# Sheet1.net
KiCad netlist of a schematic drawn in Altium Designer
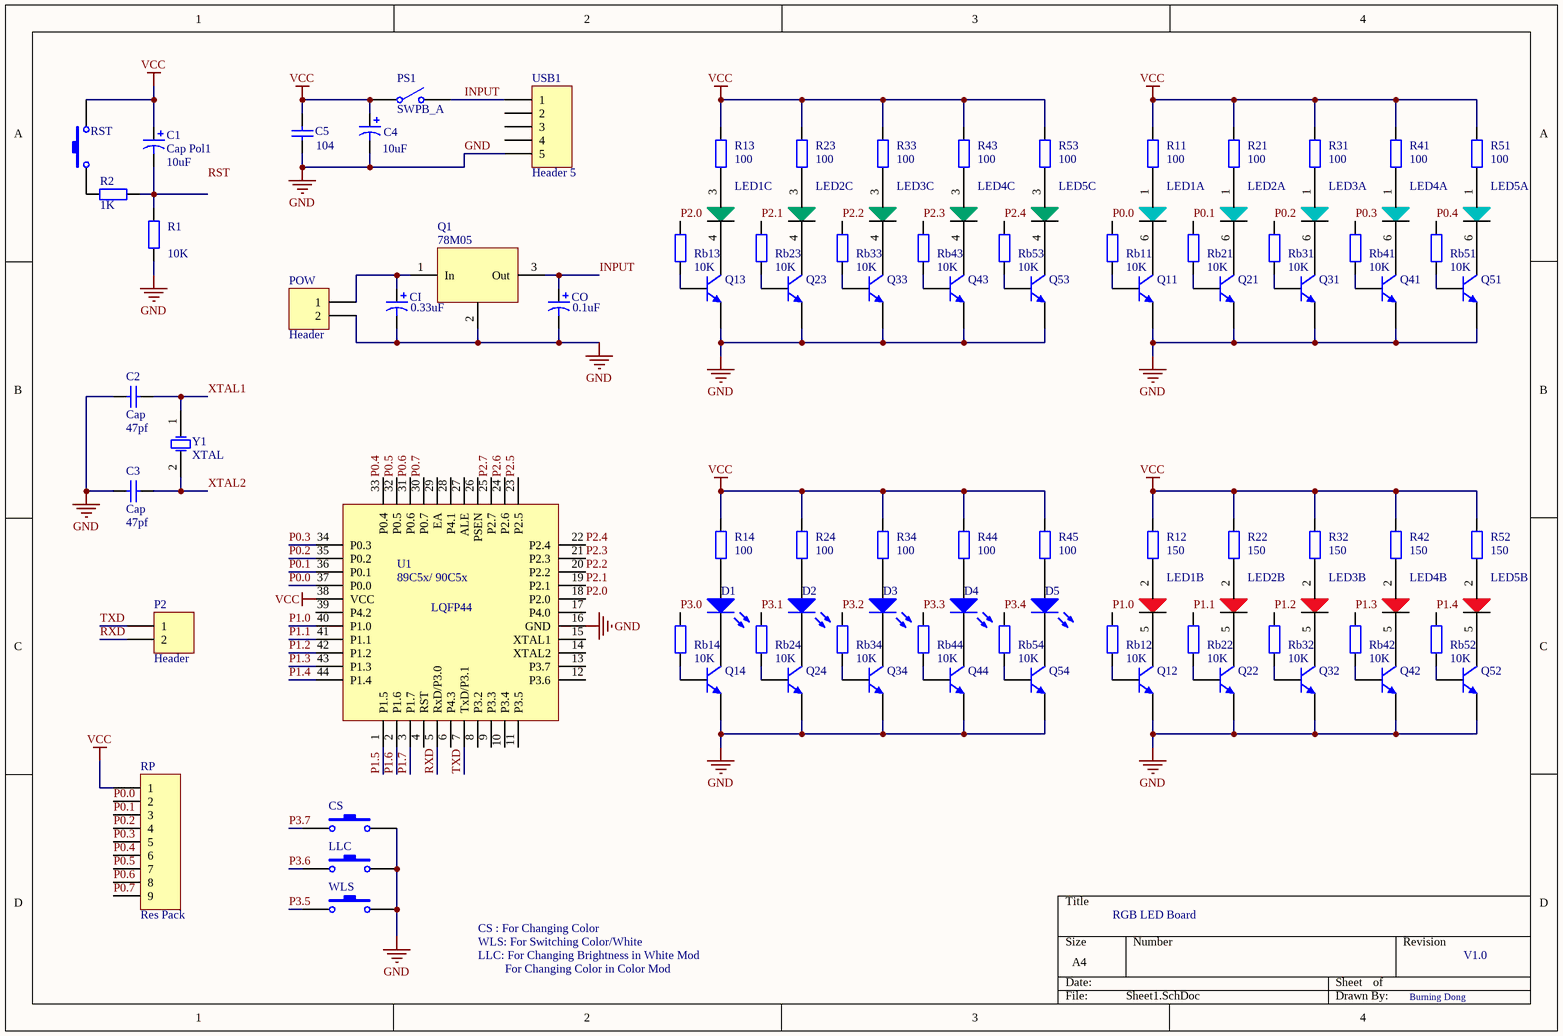
[diagram p0: Sheet1.SchDoc]

(export (version "E")
  (design (tool "Eeschema 10.0.6"))
  (components
    (comp (ref "C1")
      (value "Cap Pol1")
      (footprint "C0805")
      (description "Polarized Capacitor (Radial)")
      (fields (field (name "ALTIUM_VALUE") "10uF") (field (name "PUBLISHER") "Altium Limited"))
      (libsource (lib "Miscellaneous Devices") (part "Cap Pol1"))
    )
    (comp (ref "C2")
      (value "Cap")
      (footprint "C0805")
      (description "Capacitor")
      (fields (field (name "ALTIUM_VALUE") "47pf") (field (name "PUBLISHER") "Altium Limited"))
      (libsource (lib "Miscellaneous Devices") (part "Cap"))
    )
    (comp (ref "C3")
      (value "Cap")
      (footprint "C0805")
      (description "Capacitor")
      (fields (field (name "ALTIUM_VALUE") "47pf") (field (name "PUBLISHER") "Altium Limited"))
      (libsource (lib "Miscellaneous Devices") (part "Cap"))
    )
    (comp (ref "C4")
      (value "10uF")
      (footprint "C0805")
      (description "Polarized Capacitor (Radial)")
      (fields (field (name "Comment") "Cap Pol1") (field (name "PUBLISHER") "Altium Limited"))
      (libsource (lib "Miscellaneous Devices") (part "Cap Pol1"))
    )
    (comp (ref "C5")
      (value "104")
      (footprint "C1206")
      (description "Capacitor")
      (fields (field (name "Comment") "Cap") (field (name "PUBLISHER") "Altium Limited"))
      (libsource (lib "Miscellaneous Devices") (part "Cap"))
    )
    (comp (ref "CI")
      (value "0.33uF")
      (footprint "C0805")
      (description "Polarized Capacitor (Radial)")
      (fields (field (name "Comment") "Cap Pol1") (field (name "PUBLISHER") "Altium Limited"))
      (libsource (lib "Miscellaneous Devices") (part "Cap Pol1"))
    )
    (comp (ref "CO")
      (value "0.1uF")
      (footprint "C0805")
      (description "Polarized Capacitor (Radial)")
      (fields (field (name "Comment") "Cap Pol1") (field (name "PUBLISHER") "Altium Limited"))
      (libsource (lib "Miscellaneous Devices") (part "Cap Pol1"))
    )
    (comp (ref "CS")
      (value "SW-PB")
      (footprint "SW_A")
      (description "Switch")
      (fields (field (name "PUBLISHER") "Altium Limited"))
      (libsource (lib "Miscellaneous Devices") (part "SW-PB"))
    )
    (comp (ref "D1")
      (value "LED0")
      (footprint "LED 5050 NoneRGB")
      (description "Typical INFRARED GaAs LED")
      (fields (field (name "PUBLISHER") "Altium Limited"))
      (libsource (lib "Miscellaneous Devices") (part "LED0"))
    )
    (comp (ref "D2")
      (value "LED0")
      (footprint "LED 5050 NoneRGB")
      (description "Typical INFRARED GaAs LED")
      (fields (field (name "PUBLISHER") "Altium Limited"))
      (libsource (lib "Miscellaneous Devices") (part "LED0"))
    )
    (comp (ref "D3")
      (value "LED0")
      (footprint "LED 5050 NoneRGB")
      (description "Typical INFRARED GaAs LED")
      (fields (field (name "PUBLISHER") "Altium Limited"))
      (libsource (lib "Miscellaneous Devices") (part "LED0"))
    )
    (comp (ref "D4")
      (value "LED0")
      (footprint "LED 5050 NoneRGB")
      (description "Typical INFRARED GaAs LED")
      (fields (field (name "PUBLISHER") "Altium Limited"))
      (libsource (lib "Miscellaneous Devices") (part "LED0"))
    )
    (comp (ref "D5")
      (value "LED0")
      (footprint "LED 5050 NoneRGB")
      (description "Typical INFRARED GaAs LED")
      (fields (field (name "PUBLISHER") "Altium Limited"))
      (libsource (lib "Miscellaneous Devices") (part "LED0"))
    )
    (comp (ref "LED1") (value "RGB LED") (footprint "LED 5050") (libsource (lib "Usual") (part "RGB LED")))
    (comp (ref "LED2") (value "RGB LED") (footprint "LED 5050") (libsource (lib "Usual") (part "RGB LED")))
    (comp (ref "LED3") (value "RGB LED") (footprint "LED 5050") (libsource (lib "Usual") (part "RGB LED")))
    (comp (ref "LED4") (value "RGB LED") (footprint "LED 5050") (libsource (lib "Usual") (part "RGB LED")))
    (comp (ref "LED5") (value "RGB LED") (footprint "LED 5050") (libsource (lib "Usual") (part "RGB LED")))
    (comp (ref "LLC")
      (value "SW-PB")
      (footprint "SW_A")
      (description "Switch")
      (fields (field (name "PUBLISHER") "Altium Limited"))
      (libsource (lib "Miscellaneous Devices") (part "SW-PB"))
    )
    (comp (ref "P2")
      (value "Header")
      (footprint "HDR1X2")
      (description "Header, 2-Pin")
      (fields (field (name "PUBLISHER") "Altium Limited"))
      (libsource (lib "Miscellaneous Connectors") (part "Header 2"))
    )
    (comp (ref "POW")
      (value "Header")
      (footprint "HDR1X2")
      (description "Header, 2-Pin")
      (fields (field (name "PUBLISHER") "Altium Limited"))
      (libsource (lib "") (part "Header 2_1"))
    )
    (comp (ref "PS1")
      (value "SWPB_A")
      (footprint "SW_B")
      (description "Single-Pole, Single-Throw Switch")
      (fields (field (name "PUBLISHER") "Altium Limited"))
      (libsource (lib "Miscellaneous Devices") (part "SW-SPST"))
    )
    (comp (ref "Q1") (value "78M05") (footprint "TO_252") (libsource (lib "Usual") (part "78XX")))
    (comp (ref "Q11")
      (value "s8050")
      (footprint "SOT-23_N")
      (description "NPN General Purpose Amplifier")
      (fields (field (name "PUBLISHER") "Altium Limited"))
      (libsource (lib "Miscellaneous Devices") (part "2N3904"))
    )
    (comp (ref "Q12")
      (value "s8050")
      (footprint "SOT-23_N")
      (description "NPN General Purpose Amplifier")
      (fields (field (name "PUBLISHER") "Altium Limited"))
      (libsource (lib "Miscellaneous Devices") (part "2N3904"))
    )
    (comp (ref "Q13")
      (value "s8050")
      (footprint "SOT-23_N")
      (description "NPN General Purpose Amplifier")
      (fields (field (name "PUBLISHER") "Altium Limited"))
      (libsource (lib "Miscellaneous Devices") (part "2N3904"))
    )
    (comp (ref "Q14")
      (value "s8050")
      (footprint "SOT-23_N")
      (description "NPN General Purpose Amplifier")
      (fields (field (name "PUBLISHER") "Altium Limited"))
      (libsource (lib "Miscellaneous Devices") (part "2N3904"))
    )
    (comp (ref "Q21")
      (value "s8050")
      (footprint "SOT-23_N")
      (description "NPN General Purpose Amplifier")
      (fields (field (name "PUBLISHER") "Altium Limited"))
      (libsource (lib "Miscellaneous Devices") (part "2N3904"))
    )
    (comp (ref "Q22")
      (value "s8050")
      (footprint "SOT-23_N")
      (description "NPN General Purpose Amplifier")
      (fields (field (name "PUBLISHER") "Altium Limited"))
      (libsource (lib "Miscellaneous Devices") (part "2N3904"))
    )
    (comp (ref "Q23")
      (value "s8050")
      (footprint "SOT-23_N")
      (description "NPN General Purpose Amplifier")
      (fields (field (name "PUBLISHER") "Altium Limited"))
      (libsource (lib "Miscellaneous Devices") (part "2N3904"))
    )
    (comp (ref "Q24")
      (value "s8050")
      (footprint "SOT-23_N")
      (description "NPN General Purpose Amplifier")
      (fields (field (name "PUBLISHER") "Altium Limited"))
      (libsource (lib "Miscellaneous Devices") (part "2N3904"))
    )
    (comp (ref "Q31")
      (value "s8050")
      (footprint "SOT-23_N")
      (description "NPN General Purpose Amplifier")
      (fields (field (name "PUBLISHER") "Altium Limited"))
      (libsource (lib "Miscellaneous Devices") (part "2N3904"))
    )
    (comp (ref "Q32")
      (value "s8050")
      (footprint "SOT-23_N")
      (description "NPN General Purpose Amplifier")
      (fields (field (name "PUBLISHER") "Altium Limited"))
      (libsource (lib "Miscellaneous Devices") (part "2N3904"))
    )
    (comp (ref "Q33")
      (value "s8050")
      (footprint "SOT-23_N")
      (description "NPN General Purpose Amplifier")
      (fields (field (name "PUBLISHER") "Altium Limited"))
      (libsource (lib "Miscellaneous Devices") (part "2N3904"))
    )
    (comp (ref "Q34")
      (value "s8050")
      (footprint "SOT-23_N")
      (description "NPN General Purpose Amplifier")
      (fields (field (name "PUBLISHER") "Altium Limited"))
      (libsource (lib "Miscellaneous Devices") (part "2N3904"))
    )
    (comp (ref "Q41")
      (value "s8050")
      (footprint "SOT-23_N")
      (description "NPN General Purpose Amplifier")
      (fields (field (name "PUBLISHER") "Altium Limited"))
      (libsource (lib "Miscellaneous Devices") (part "2N3904"))
    )
    (comp (ref "Q42")
      (value "s8050")
      (footprint "SOT-23_N")
      (description "NPN General Purpose Amplifier")
      (fields (field (name "PUBLISHER") "Altium Limited"))
      (libsource (lib "Miscellaneous Devices") (part "2N3904"))
    )
    (comp (ref "Q43")
      (value "s8050")
      (footprint "SOT-23_N")
      (description "NPN General Purpose Amplifier")
      (fields (field (name "PUBLISHER") "Altium Limited"))
      (libsource (lib "Miscellaneous Devices") (part "2N3904"))
    )
    (comp (ref "Q44")
      (value "s8050")
      (footprint "SOT-23_N")
      (description "NPN General Purpose Amplifier")
      (fields (field (name "PUBLISHER") "Altium Limited"))
      (libsource (lib "Miscellaneous Devices") (part "2N3904"))
    )
    (comp (ref "Q51")
      (value "s8050")
      (footprint "SOT-23_N")
      (description "NPN General Purpose Amplifier")
      (fields (field (name "PUBLISHER") "Altium Limited"))
      (libsource (lib "Miscellaneous Devices") (part "2N3904"))
    )
    (comp (ref "Q52")
      (value "s8050")
      (footprint "SOT-23_N")
      (description "NPN General Purpose Amplifier")
      (fields (field (name "PUBLISHER") "Altium Limited"))
      (libsource (lib "Miscellaneous Devices") (part "2N3904"))
    )
    (comp (ref "Q53")
      (value "s8050")
      (footprint "SOT-23_N")
      (description "NPN General Purpose Amplifier")
      (fields (field (name "PUBLISHER") "Altium Limited"))
      (libsource (lib "Miscellaneous Devices") (part "2N3904"))
    )
    (comp (ref "Q54")
      (value "s8050")
      (footprint "SOT-23_N")
      (description "NPN General Purpose Amplifier")
      (fields (field (name "PUBLISHER") "Altium Limited"))
      (libsource (lib "Miscellaneous Devices") (part "2N3904"))
    )
    (comp (ref "R1")
      (value "10K")
      (footprint "6-0805_N")
      (description "Resistor")
      (fields (field (name "Comment") "Res2") (field (name "PUBLISHER") "Altium Limited"))
      (libsource (lib "Miscellaneous Devices") (part "Res2"))
    )
    (comp (ref "R2")
      (value "1K")
      (footprint "6-0805_N")
      (description "Resistor")
      (fields (field (name "Comment") "Res2") (field (name "PUBLISHER") "Altium Limited"))
      (libsource (lib "") (part "Res2_1"))
    )
    (comp (ref "R11")
      (value "100")
      (footprint "6-0805_N")
      (description "Resistor")
      (fields (field (name "Comment") "Res2") (field (name "PUBLISHER") "Altium Limited"))
      (libsource (lib "Miscellaneous Devices") (part "Res2"))
    )
    (comp (ref "R12")
      (value "150")
      (footprint "6-0805_N")
      (description "Resistor")
      (fields (field (name "Comment") "Res2") (field (name "PUBLISHER") "Altium Limited"))
      (libsource (lib "Miscellaneous Devices") (part "Res2"))
    )
    (comp (ref "R13")
      (value "100")
      (footprint "6-0805_N")
      (description "Resistor")
      (fields (field (name "Comment") "Res2") (field (name "PUBLISHER") "Altium Limited"))
      (libsource (lib "Miscellaneous Devices") (part "Res2"))
    )
    (comp (ref "R14")
      (value "100")
      (footprint "6-0805_N")
      (description "Resistor")
      (fields (field (name "Comment") "Res2") (field (name "PUBLISHER") "Altium Limited"))
      (libsource (lib "Miscellaneous Devices") (part "Res2"))
    )
    (comp (ref "R21")
      (value "100")
      (footprint "6-0805_N")
      (description "Resistor")
      (fields (field (name "Comment") "Res2") (field (name "PUBLISHER") "Altium Limited"))
      (libsource (lib "Miscellaneous Devices") (part "Res2"))
    )
    (comp (ref "R22")
      (value "150")
      (footprint "6-0805_N")
      (description "Resistor")
      (fields (field (name "Comment") "Res2") (field (name "PUBLISHER") "Altium Limited"))
      (libsource (lib "Miscellaneous Devices") (part "Res2"))
    )
    (comp (ref "R23")
      (value "100")
      (footprint "6-0805_N")
      (description "Resistor")
      (fields (field (name "Comment") "Res2") (field (name "PUBLISHER") "Altium Limited"))
      (libsource (lib "Miscellaneous Devices") (part "Res2"))
    )
    (comp (ref "R24")
      (value "100")
      (footprint "6-0805_N")
      (description "Resistor")
      (fields (field (name "Comment") "Res2") (field (name "PUBLISHER") "Altium Limited"))
      (libsource (lib "Miscellaneous Devices") (part "Res2"))
    )
    (comp (ref "R31")
      (value "100")
      (footprint "6-0805_N")
      (description "Resistor")
      (fields (field (name "Comment") "Res2") (field (name "PUBLISHER") "Altium Limited"))
      (libsource (lib "Miscellaneous Devices") (part "Res2"))
    )
    (comp (ref "R32")
      (value "150")
      (footprint "6-0805_N")
      (description "Resistor")
      (fields (field (name "Comment") "Res2") (field (name "PUBLISHER") "Altium Limited"))
      (libsource (lib "Miscellaneous Devices") (part "Res2"))
    )
    (comp (ref "R33")
      (value "100")
      (footprint "6-0805_N")
      (description "Resistor")
      (fields (field (name "Comment") "Res2") (field (name "PUBLISHER") "Altium Limited"))
      (libsource (lib "Miscellaneous Devices") (part "Res2"))
    )
    (comp (ref "R34")
      (value "100")
      (footprint "6-0805_N")
      (description "Resistor")
      (fields (field (name "Comment") "Res2") (field (name "PUBLISHER") "Altium Limited"))
      (libsource (lib "Miscellaneous Devices") (part "Res2"))
    )
    (comp (ref "R41")
      (value "100")
      (footprint "6-0805_N")
      (description "Resistor")
      (fields (field (name "Comment") "Res2") (field (name "PUBLISHER") "Altium Limited"))
      (libsource (lib "Miscellaneous Devices") (part "Res2"))
    )
    (comp (ref "R42")
      (value "150")
      (footprint "6-0805_N")
      (description "Resistor")
      (fields (field (name "Comment") "Res2") (field (name "PUBLISHER") "Altium Limited"))
      (libsource (lib "Miscellaneous Devices") (part "Res2"))
    )
    (comp (ref "R43")
      (value "100")
      (footprint "6-0805_N")
      (description "Resistor")
      (fields (field (name "Comment") "Res2") (field (name "PUBLISHER") "Altium Limited"))
      (libsource (lib "Miscellaneous Devices") (part "Res2"))
    )
    (comp (ref "R44")
      (value "100")
      (footprint "6-0805_N")
      (description "Resistor")
      (fields (field (name "Comment") "Res2") (field (name "PUBLISHER") "Altium Limited"))
      (libsource (lib "Miscellaneous Devices") (part "Res2"))
    )
    (comp (ref "R45")
      (value "100")
      (footprint "6-0805_N")
      (description "Resistor")
      (fields (field (name "Comment") "Res2") (field (name "PUBLISHER") "Altium Limited"))
      (libsource (lib "Miscellaneous Devices") (part "Res2"))
    )
    (comp (ref "R51")
      (value "100")
      (footprint "6-0805_N")
      (description "Resistor")
      (fields (field (name "Comment") "Res2") (field (name "PUBLISHER") "Altium Limited"))
      (libsource (lib "Miscellaneous Devices") (part "Res2"))
    )
    (comp (ref "R52")
      (value "150")
      (footprint "6-0805_N")
      (description "Resistor")
      (fields (field (name "Comment") "Res2") (field (name "PUBLISHER") "Altium Limited"))
      (libsource (lib "Miscellaneous Devices") (part "Res2"))
    )
    (comp (ref "R53")
      (value "100")
      (footprint "6-0805_N")
      (description "Resistor")
      (fields (field (name "Comment") "Res2") (field (name "PUBLISHER") "Altium Limited"))
      (libsource (lib "Miscellaneous Devices") (part "Res2"))
    )
    (comp (ref "Rb11")
      (value "10K")
      (footprint "6-0805_N")
      (description "Resistor")
      (fields (field (name "Comment") "Res2") (field (name "PUBLISHER") "Altium Limited"))
      (libsource (lib "Miscellaneous Devices") (part "Res2"))
    )
    (comp (ref "Rb12")
      (value "10K")
      (footprint "6-0805_N")
      (description "Resistor")
      (fields (field (name "Comment") "Res2") (field (name "PUBLISHER") "Altium Limited"))
      (libsource (lib "Miscellaneous Devices") (part "Res2"))
    )
    (comp (ref "Rb13")
      (value "10K")
      (footprint "6-0805_N")
      (description "Resistor")
      (fields (field (name "Comment") "Res2") (field (name "PUBLISHER") "Altium Limited"))
      (libsource (lib "Miscellaneous Devices") (part "Res2"))
    )
    (comp (ref "Rb14")
      (value "10K")
      (footprint "6-0805_N")
      (description "Resistor")
      (fields (field (name "Comment") "Res2") (field (name "PUBLISHER") "Altium Limited"))
      (libsource (lib "Miscellaneous Devices") (part "Res2"))
    )
    (comp (ref "Rb21")
      (value "10K")
      (footprint "6-0805_N")
      (description "Resistor")
      (fields (field (name "Comment") "Res2") (field (name "PUBLISHER") "Altium Limited"))
      (libsource (lib "Miscellaneous Devices") (part "Res2"))
    )
    (comp (ref "Rb22")
      (value "10K")
      (footprint "6-0805_N")
      (description "Resistor")
      (fields (field (name "Comment") "Res2") (field (name "PUBLISHER") "Altium Limited"))
      (libsource (lib "Miscellaneous Devices") (part "Res2"))
    )
    (comp (ref "Rb23")
      (value "10K")
      (footprint "6-0805_N")
      (description "Resistor")
      (fields (field (name "Comment") "Res2") (field (name "PUBLISHER") "Altium Limited"))
      (libsource (lib "Miscellaneous Devices") (part "Res2"))
    )
    (comp (ref "Rb24")
      (value "10K")
      (footprint "6-0805_N")
      (description "Resistor")
      (fields (field (name "Comment") "Res2") (field (name "PUBLISHER") "Altium Limited"))
      (libsource (lib "Miscellaneous Devices") (part "Res2"))
    )
    (comp (ref "Rb31")
      (value "10K")
      (footprint "6-0805_N")
      (description "Resistor")
      (fields (field (name "Comment") "Res2") (field (name "PUBLISHER") "Altium Limited"))
      (libsource (lib "Miscellaneous Devices") (part "Res2"))
    )
    (comp (ref "Rb32")
      (value "10K")
      (footprint "6-0805_N")
      (description "Resistor")
      (fields (field (name "Comment") "Res2") (field (name "PUBLISHER") "Altium Limited"))
      (libsource (lib "Miscellaneous Devices") (part "Res2"))
    )
    (comp (ref "Rb33")
      (value "10K")
      (footprint "6-0805_N")
      (description "Resistor")
      (fields (field (name "Comment") "Res2") (field (name "PUBLISHER") "Altium Limited"))
      (libsource (lib "Miscellaneous Devices") (part "Res2"))
    )
    (comp (ref "Rb34")
      (value "10K")
      (footprint "6-0805_N")
      (description "Resistor")
      (fields (field (name "Comment") "Res2") (field (name "PUBLISHER") "Altium Limited"))
      (libsource (lib "Miscellaneous Devices") (part "Res2"))
    )
    (comp (ref "Rb41")
      (value "10K")
      (footprint "6-0805_N")
      (description "Resistor")
      (fields (field (name "Comment") "Res2") (field (name "PUBLISHER") "Altium Limited"))
      (libsource (lib "Miscellaneous Devices") (part "Res2"))
    )
    (comp (ref "Rb42")
      (value "10K")
      (footprint "6-0805_N")
      (description "Resistor")
      (fields (field (name "Comment") "Res2") (field (name "PUBLISHER") "Altium Limited"))
      (libsource (lib "Miscellaneous Devices") (part "Res2"))
    )
    (comp (ref "Rb43")
      (value "10K")
      (footprint "6-0805_N")
      (description "Resistor")
      (fields (field (name "Comment") "Res2") (field (name "PUBLISHER") "Altium Limited"))
      (libsource (lib "Miscellaneous Devices") (part "Res2"))
    )
    (comp (ref "Rb44")
      (value "10K")
      (footprint "6-0805_N")
      (description "Resistor")
      (fields (field (name "Comment") "Res2") (field (name "PUBLISHER") "Altium Limited"))
      (libsource (lib "Miscellaneous Devices") (part "Res2"))
    )
    (comp (ref "Rb51")
      (value "10K")
      (footprint "6-0805_N")
      (description "Resistor")
      (fields (field (name "Comment") "Res2") (field (name "PUBLISHER") "Altium Limited"))
      (libsource (lib "Miscellaneous Devices") (part "Res2"))
    )
    (comp (ref "Rb52")
      (value "10K")
      (footprint "6-0805_N")
      (description "Resistor")
      (fields (field (name "Comment") "Res2") (field (name "PUBLISHER") "Altium Limited"))
      (libsource (lib "Miscellaneous Devices") (part "Res2"))
    )
    (comp (ref "Rb53")
      (value "10K")
      (footprint "6-0805_N")
      (description "Resistor")
      (fields (field (name "Comment") "Res2") (field (name "PUBLISHER") "Altium Limited"))
      (libsource (lib "Miscellaneous Devices") (part "Res2"))
    )
    (comp (ref "Rb54")
      (value "10K")
      (footprint "6-0805_N")
      (description "Resistor")
      (fields (field (name "Comment") "Res2") (field (name "PUBLISHER") "Altium Limited"))
      (libsource (lib "Miscellaneous Devices") (part "Res2"))
    )
    (comp (ref "RP")
      (value "Res Pack")
      (footprint "HDR1X9")
      (description "Header, 9-Pin")
      (fields (field (name "PUBLISHER") "Altium Limited"))
      (libsource (lib "Miscellaneous Connectors") (part "Header 9"))
    )
    (comp (ref "RST")
      (value "SW-PB")
      (footprint "SW_A")
      (description "Switch")
      (fields (field (name "PUBLISHER") "Altium Limited"))
      (libsource (lib "Miscellaneous Devices") (part "SW-PB"))
    )
    (comp (ref "U1")
      (value "89C5x/ 90C5x")
      (footprint "TQFP44_N")
      (libsource (lib "STC") (part "89C5x/ 90C5x"))
    )
    (comp (ref "USB1")
      (value "Header 5")
      (footprint "Micro_USB_B")
      (description "Header, 5-Pin")
      (fields (field (name "PUBLISHER") "Altium Limited"))
      (libsource (lib "Miscellaneous Connectors") (part "Header 5"))
    )
    (comp (ref "WLS")
      (value "SW-PB")
      (footprint "SW_A")
      (description "Switch")
      (fields (field (name "PUBLISHER") "Altium Limited"))
      (libsource (lib "Miscellaneous Devices") (part "SW-PB"))
    )
    (comp (ref "Y1")
      (value "XTAL")
      (footprint "XTAL")
      (description "Crystal Oscillator")
      (fields (field (name "PUBLISHER") "Altium Limited"))
      (libsource (lib "Miscellaneous Devices") (part "XTAL"))
    )
  )
  (nets
    (net (code "1") (name "/INPUT") (class "Default")
      (node (ref "CO") (pin "1") (pinfunction "1_1") (pintype "passive"))
      (node (ref "PS1") (pin "2") (pinfunction "NO_2") (pintype "passive"))
      (node (ref "Q1") (pin "3") (pinfunction "Out_3") (pintype "passive"))
      (node (ref "USB1") (pin "1") (pinfunction "1_1") (pintype "passive"))
    )
    (net (code "2") (name "/P0.0") (class "Default")
      (node (ref "RP") (pin "2") (pinfunction "2_2") (pintype "passive"))
      (node (ref "Rb11") (pin "1") (pinfunction "1_1") (pintype "passive"))
      (node (ref "U1") (pin "37") (pinfunction "P0.0_37") (pintype "passive"))
    )
    (net (code "3") (name "/P0.1") (class "Default")
      (node (ref "RP") (pin "3") (pinfunction "3_3") (pintype "passive"))
      (node (ref "Rb21") (pin "1") (pinfunction "1_1") (pintype "passive"))
      (node (ref "U1") (pin "36") (pinfunction "P0.1_36") (pintype "passive"))
    )
    (net (code "4") (name "/P0.2") (class "Default")
      (node (ref "RP") (pin "4") (pinfunction "4_4") (pintype "passive"))
      (node (ref "Rb31") (pin "1") (pinfunction "1_1") (pintype "passive"))
      (node (ref "U1") (pin "35") (pinfunction "P0.2_35") (pintype "passive"))
    )
    (net (code "5") (name "/P0.3") (class "Default")
      (node (ref "RP") (pin "5") (pinfunction "5_5") (pintype "passive"))
      (node (ref "Rb41") (pin "1") (pinfunction "1_1") (pintype "passive"))
      (node (ref "U1") (pin "34") (pinfunction "P0.3_34") (pintype "passive"))
    )
    (net (code "6") (name "/P0.4") (class "Default")
      (node (ref "RP") (pin "6") (pinfunction "6_6") (pintype "passive"))
      (node (ref "Rb51") (pin "1") (pinfunction "1_1") (pintype "passive"))
      (node (ref "U1") (pin "33") (pinfunction "P0.4_33") (pintype "passive"))
    )
    (net (code "7") (name "/P0.5") (class "Default")
      (node (ref "RP") (pin "7") (pinfunction "7_7") (pintype "passive"))
      (node (ref "U1") (pin "32") (pinfunction "P0.5_32") (pintype "passive"))
    )
    (net (code "8") (name "/P0.6") (class "Default")
      (node (ref "RP") (pin "8") (pinfunction "8_8") (pintype "passive"))
      (node (ref "U1") (pin "31") (pinfunction "P0.6_31") (pintype "passive"))
    )
    (net (code "9") (name "/P0.7") (class "Default")
      (node (ref "RP") (pin "9") (pinfunction "9_9") (pintype "passive"))
      (node (ref "U1") (pin "30") (pinfunction "P0.7_30") (pintype "passive"))
    )
    (net (code "10") (name "/P1.0") (class "Default")
      (node (ref "Rb12") (pin "1") (pinfunction "1_1") (pintype "passive"))
      (node (ref "U1") (pin "40") (pinfunction "P1.0_40") (pintype "passive"))
    )
    (net (code "11") (name "/P1.1") (class "Default")
      (node (ref "Rb22") (pin "1") (pinfunction "1_1") (pintype "passive"))
      (node (ref "U1") (pin "41") (pinfunction "P1.1_41") (pintype "passive"))
    )
    (net (code "12") (name "/P1.2") (class "Default")
      (node (ref "Rb32") (pin "1") (pinfunction "1_1") (pintype "passive"))
      (node (ref "U1") (pin "42") (pinfunction "P1.2_42") (pintype "passive"))
    )
    (net (code "13") (name "/P1.3") (class "Default")
      (node (ref "Rb42") (pin "1") (pinfunction "1_1") (pintype "passive"))
      (node (ref "U1") (pin "43") (pinfunction "P1.3_43") (pintype "passive"))
    )
    (net (code "14") (name "/P1.4") (class "Default")
      (node (ref "Rb52") (pin "1") (pinfunction "1_1") (pintype "passive"))
      (node (ref "U1") (pin "44") (pinfunction "P1.4_44") (pintype "passive"))
    )
    (net (code "15") (name "/P1.5") (class "Default")
      (node (ref "U1") (pin "1") (pinfunction "P1.5_1") (pintype "passive"))
    )
    (net (code "16") (name "/P1.6") (class "Default")
      (node (ref "U1") (pin "2") (pinfunction "P1.6_2") (pintype "passive"))
    )
    (net (code "17") (name "/P1.7") (class "Default")
      (node (ref "U1") (pin "3") (pinfunction "P1.7_3") (pintype "passive"))
    )
    (net (code "18") (name "/P2.0") (class "Default")
      (node (ref "Rb13") (pin "1") (pinfunction "1_1") (pintype "passive"))
      (node (ref "U1") (pin "18") (pinfunction "P2.0_18") (pintype "passive"))
    )
    (net (code "19") (name "/P2.1") (class "Default")
      (node (ref "Rb23") (pin "1") (pinfunction "1_1") (pintype "passive"))
      (node (ref "U1") (pin "19") (pinfunction "P2.1_19") (pintype "passive"))
    )
    (net (code "20") (name "/P2.2") (class "Default")
      (node (ref "Rb33") (pin "1") (pinfunction "1_1") (pintype "passive"))
      (node (ref "U1") (pin "20") (pinfunction "P2.2_20") (pintype "passive"))
    )
    (net (code "21") (name "/P2.3") (class "Default")
      (node (ref "Rb43") (pin "1") (pinfunction "1_1") (pintype "passive"))
      (node (ref "U1") (pin "21") (pinfunction "P2.3_21") (pintype "passive"))
    )
    (net (code "22") (name "/P2.4") (class "Default")
      (node (ref "Rb53") (pin "1") (pinfunction "1_1") (pintype "passive"))
      (node (ref "U1") (pin "22") (pinfunction "P2.4_22") (pintype "passive"))
    )
    (net (code "23") (name "/P2.5") (class "Default")
      (node (ref "U1") (pin "23") (pinfunction "P2.5_23") (pintype "passive"))
    )
    (net (code "24") (name "/P2.6") (class "Default")
      (node (ref "U1") (pin "24") (pinfunction "P2.6_24") (pintype "passive"))
    )
    (net (code "25") (name "/P2.7") (class "Default")
      (node (ref "U1") (pin "25") (pinfunction "P2.7_25") (pintype "passive"))
    )
    (net (code "26") (name "/P3.0") (class "Default")
      (node (ref "Rb14") (pin "1") (pinfunction "1_1") (pintype "passive"))
    )
    (net (code "27") (name "/P3.1") (class "Default")
      (node (ref "Rb24") (pin "1") (pinfunction "1_1") (pintype "passive"))
    )
    (net (code "28") (name "/P3.2") (class "Default")
      (node (ref "Rb34") (pin "1") (pinfunction "1_1") (pintype "passive"))
    )
    (net (code "29") (name "/P3.3") (class "Default")
      (node (ref "Rb44") (pin "1") (pinfunction "1_1") (pintype "passive"))
    )
    (net (code "30") (name "/P3.4") (class "Default")
      (node (ref "Rb54") (pin "1") (pinfunction "1_1") (pintype "passive"))
    )
    (net (code "31") (name "/P3.5") (class "Default")
      (node (ref "WLS") (pin "1") (pinfunction "1_1") (pintype "passive"))
    )
    (net (code "32") (name "/P3.6") (class "Default")
      (node (ref "LLC") (pin "1") (pinfunction "1_1") (pintype "passive"))
    )
    (net (code "33") (name "/P3.7") (class "Default")
      (node (ref "CS") (pin "1") (pinfunction "1_1") (pintype "passive"))
    )
    (net (code "35") (name "/RXD") (class "Default")
      (node (ref "P2") (pin "2") (pinfunction "2_2") (pintype "passive"))
      (node (ref "U1") (pin "5") (pinfunction "RxD/P3.0_5") (pintype "passive"))
    )
    (net (code "36") (name "/TXD") (class "Default")
      (node (ref "P2") (pin "1") (pinfunction "1_1") (pintype "passive"))
      (node (ref "U1") (pin "7") (pinfunction "TxD/P3.1_7") (pintype "passive"))
    )
    (net (code "37") (name "/XTAL1") (class "Default")
      (node (ref "C2") (pin "2") (pinfunction "2_2") (pintype "passive"))
      (node (ref "Y1") (pin "1") (pinfunction "OSC1_1") (pintype "passive"))
    )
    (net (code "38") (name "/XTAL2") (class "Default")
      (node (ref "C3") (pin "2") (pinfunction "2_2") (pintype "passive"))
      (node (ref "Y1") (pin "2") (pinfunction "OSC2_2") (pintype "passive"))
    )
    (net (code "39") (name "GND") (class "Default")
      (node (ref "C2") (pin "1") (pinfunction "1_1") (pintype "passive"))
      (node (ref "C3") (pin "1") (pinfunction "1_1") (pintype "passive"))
      (node (ref "C4") (pin "2") (pinfunction "2_2") (pintype "passive"))
      (node (ref "C5") (pin "2") (pinfunction "2_2") (pintype "passive"))
      (node (ref "CI") (pin "2") (pinfunction "2_2") (pintype "passive"))
      (node (ref "CO") (pin "2") (pinfunction "2_2") (pintype "passive"))
      (node (ref "CS") (pin "2") (pinfunction "2_2") (pintype "passive"))
      (node (ref "LLC") (pin "2") (pinfunction "2_2") (pintype "passive"))
      (node (ref "POW") (pin "2") (pinfunction "2_2") (pintype "passive"))
      (node (ref "Q1") (pin "2") (pinfunction "Com_2") (pintype "passive"))
      (node (ref "Q11") (pin "1") (pinfunction "E_1") (pintype "passive"))
      (node (ref "Q12") (pin "1") (pinfunction "E_1") (pintype "passive"))
      (node (ref "Q13") (pin "1") (pinfunction "E_1") (pintype "passive"))
      (node (ref "Q14") (pin "1") (pinfunction "E_1") (pintype "passive"))
      (node (ref "Q21") (pin "1") (pinfunction "E_1") (pintype "passive"))
      (node (ref "Q22") (pin "1") (pinfunction "E_1") (pintype "passive"))
      (node (ref "Q23") (pin "1") (pinfunction "E_1") (pintype "passive"))
      (node (ref "Q24") (pin "1") (pinfunction "E_1") (pintype "passive"))
      (node (ref "Q31") (pin "1") (pinfunction "E_1") (pintype "passive"))
      (node (ref "Q32") (pin "1") (pinfunction "E_1") (pintype "passive"))
      (node (ref "Q33") (pin "1") (pinfunction "E_1") (pintype "passive"))
      (node (ref "Q34") (pin "1") (pinfunction "E_1") (pintype "passive"))
      (node (ref "Q41") (pin "1") (pinfunction "E_1") (pintype "passive"))
      (node (ref "Q42") (pin "1") (pinfunction "E_1") (pintype "passive"))
      (node (ref "Q43") (pin "1") (pinfunction "E_1") (pintype "passive"))
      (node (ref "Q44") (pin "1") (pinfunction "E_1") (pintype "passive"))
      (node (ref "Q51") (pin "1") (pinfunction "E_1") (pintype "passive"))
      (node (ref "Q52") (pin "1") (pinfunction "E_1") (pintype "passive"))
      (node (ref "Q53") (pin "1") (pinfunction "E_1") (pintype "passive"))
      (node (ref "Q54") (pin "1") (pinfunction "E_1") (pintype "passive"))
      (node (ref "R1") (pin "2") (pinfunction "2_2") (pintype "passive"))
      (node (ref "U1") (pin "16") (pinfunction "GND_16") (pintype "passive"))
      (node (ref "USB1") (pin "5") (pinfunction "5_5") (pintype "passive"))
      (node (ref "WLS") (pin "2") (pinfunction "2_2") (pintype "passive"))
    )
    (net (code "40") (name "Net-(C1-Pad2)") (class "Default")
      (node (ref "C1") (pin "2") (pinfunction "2_2") (pintype "passive"))
      (node (ref "R1") (pin "1") (pinfunction "1_1") (pintype "passive"))
      (node (ref "R2") (pin "1") (pinfunction "1_1") (pintype "passive"))
    )
    (net (code "41") (name "Net-(D1-A)") (class "Default")
      (node (ref "D1") (pin "1") (pinfunction "A_1") (pintype "passive"))
      (node (ref "R14") (pin "2") (pinfunction "2_2") (pintype "passive"))
    )
    (net (code "42") (name "Net-(D1-K)") (class "Default")
      (node (ref "D1") (pin "2") (pinfunction "K_2") (pintype "passive"))
      (node (ref "Q14") (pin "3") (pinfunction "C_3") (pintype "passive"))
    )
    (net (code "43") (name "Net-(D2-A)") (class "Default")
      (node (ref "D2") (pin "1") (pinfunction "A_1") (pintype "passive"))
      (node (ref "R24") (pin "2") (pinfunction "2_2") (pintype "passive"))
    )
    (net (code "44") (name "Net-(D2-K)") (class "Default")
      (node (ref "D2") (pin "2") (pinfunction "K_2") (pintype "passive"))
      (node (ref "Q24") (pin "3") (pinfunction "C_3") (pintype "passive"))
    )
    (net (code "45") (name "Net-(D3-A)") (class "Default")
      (node (ref "D3") (pin "1") (pinfunction "A_1") (pintype "passive"))
      (node (ref "R34") (pin "2") (pinfunction "2_2") (pintype "passive"))
    )
    (net (code "46") (name "Net-(D3-K)") (class "Default")
      (node (ref "D3") (pin "2") (pinfunction "K_2") (pintype "passive"))
      (node (ref "Q34") (pin "3") (pinfunction "C_3") (pintype "passive"))
    )
    (net (code "47") (name "Net-(D4-A)") (class "Default")
      (node (ref "D4") (pin "1") (pinfunction "A_1") (pintype "passive"))
      (node (ref "R44") (pin "2") (pinfunction "2_2") (pintype "passive"))
    )
    (net (code "48") (name "Net-(D4-K)") (class "Default")
      (node (ref "D4") (pin "2") (pinfunction "K_2") (pintype "passive"))
      (node (ref "Q44") (pin "3") (pinfunction "C_3") (pintype "passive"))
    )
    (net (code "49") (name "Net-(D5-A)") (class "Default")
      (node (ref "D5") (pin "1") (pinfunction "A_1") (pintype "passive"))
      (node (ref "R45") (pin "2") (pinfunction "2_2") (pintype "passive"))
    )
    (net (code "50") (name "Net-(D5-K)") (class "Default")
      (node (ref "D5") (pin "2") (pinfunction "K_2") (pintype "passive"))
      (node (ref "Q54") (pin "3") (pinfunction "C_3") (pintype "passive"))
    )
    (net (code "51") (name "Net-(LED1A-B+)") (class "Default")
      (node (ref "LED1") (pin "1") (pinfunction "B+_1") (pintype "passive"))
      (node (ref "R11") (pin "2") (pinfunction "2_2") (pintype "passive"))
    )
    (net (code "52") (name "Net-(LED1A-B-)") (class "Default")
      (node (ref "LED1") (pin "6") (pinfunction "B-_6") (pintype "passive"))
      (node (ref "Q11") (pin "3") (pinfunction "C_3") (pintype "passive"))
    )
    (net (code "53") (name "Net-(LED1B-B+)") (class "Default")
      (node (ref "LED1") (pin "2") (pinfunction "B+_2") (pintype "passive"))
      (node (ref "R12") (pin "2") (pinfunction "2_2") (pintype "passive"))
    )
    (net (code "54") (name "Net-(LED1B-B-)") (class "Default")
      (node (ref "LED1") (pin "5") (pinfunction "B-_5") (pintype "passive"))
      (node (ref "Q12") (pin "3") (pinfunction "C_3") (pintype "passive"))
    )
    (net (code "55") (name "Net-(LED1C-B+)") (class "Default")
      (node (ref "LED1") (pin "3") (pinfunction "B+_3") (pintype "passive"))
      (node (ref "R13") (pin "2") (pinfunction "2_2") (pintype "passive"))
    )
    (net (code "56") (name "Net-(LED1C-B-)") (class "Default")
      (node (ref "LED1") (pin "4") (pinfunction "B-_4") (pintype "passive"))
      (node (ref "Q13") (pin "3") (pinfunction "C_3") (pintype "passive"))
    )
    (net (code "57") (name "Net-(LED2A-B+)") (class "Default")
      (node (ref "LED2") (pin "1") (pinfunction "B+_1") (pintype "passive"))
      (node (ref "R21") (pin "2") (pinfunction "2_2") (pintype "passive"))
    )
    (net (code "58") (name "Net-(LED2A-B-)") (class "Default")
      (node (ref "LED2") (pin "6") (pinfunction "B-_6") (pintype "passive"))
      (node (ref "Q21") (pin "3") (pinfunction "C_3") (pintype "passive"))
    )
    (net (code "59") (name "Net-(LED2B-B+)") (class "Default")
      (node (ref "LED2") (pin "2") (pinfunction "B+_2") (pintype "passive"))
      (node (ref "R22") (pin "2") (pinfunction "2_2") (pintype "passive"))
    )
    (net (code "60") (name "Net-(LED2B-B-)") (class "Default")
      (node (ref "LED2") (pin "5") (pinfunction "B-_5") (pintype "passive"))
      (node (ref "Q22") (pin "3") (pinfunction "C_3") (pintype "passive"))
    )
    (net (code "61") (name "Net-(LED2C-B+)") (class "Default")
      (node (ref "LED2") (pin "3") (pinfunction "B+_3") (pintype "passive"))
      (node (ref "R23") (pin "2") (pinfunction "2_2") (pintype "passive"))
    )
    (net (code "62") (name "Net-(LED2C-B-)") (class "Default")
      (node (ref "LED2") (pin "4") (pinfunction "B-_4") (pintype "passive"))
      (node (ref "Q23") (pin "3") (pinfunction "C_3") (pintype "passive"))
    )
    (net (code "63") (name "Net-(LED3A-B+)") (class "Default")
      (node (ref "LED3") (pin "1") (pinfunction "B+_1") (pintype "passive"))
      (node (ref "R31") (pin "2") (pinfunction "2_2") (pintype "passive"))
    )
    (net (code "64") (name "Net-(LED3A-B-)") (class "Default")
      (node (ref "LED3") (pin "6") (pinfunction "B-_6") (pintype "passive"))
      (node (ref "Q31") (pin "3") (pinfunction "C_3") (pintype "passive"))
    )
    (net (code "65") (name "Net-(LED3B-B+)") (class "Default")
      (node (ref "LED3") (pin "2") (pinfunction "B+_2") (pintype "passive"))
      (node (ref "R32") (pin "2") (pinfunction "2_2") (pintype "passive"))
    )
    (net (code "66") (name "Net-(LED3B-B-)") (class "Default")
      (node (ref "LED3") (pin "5") (pinfunction "B-_5") (pintype "passive"))
      (node (ref "Q32") (pin "3") (pinfunction "C_3") (pintype "passive"))
    )
    (net (code "67") (name "Net-(LED3C-B+)") (class "Default")
      (node (ref "LED3") (pin "3") (pinfunction "B+_3") (pintype "passive"))
      (node (ref "R33") (pin "2") (pinfunction "2_2") (pintype "passive"))
    )
    (net (code "68") (name "Net-(LED3C-B-)") (class "Default")
      (node (ref "LED3") (pin "4") (pinfunction "B-_4") (pintype "passive"))
      (node (ref "Q33") (pin "3") (pinfunction "C_3") (pintype "passive"))
    )
    (net (code "69") (name "Net-(LED4A-B+)") (class "Default")
      (node (ref "LED4") (pin "1") (pinfunction "B+_1") (pintype "passive"))
      (node (ref "R41") (pin "2") (pinfunction "2_2") (pintype "passive"))
    )
    (net (code "70") (name "Net-(LED4A-B-)") (class "Default")
      (node (ref "LED4") (pin "6") (pinfunction "B-_6") (pintype "passive"))
      (node (ref "Q41") (pin "3") (pinfunction "C_3") (pintype "passive"))
    )
    (net (code "71") (name "Net-(LED4B-B+)") (class "Default")
      (node (ref "LED4") (pin "2") (pinfunction "B+_2") (pintype "passive"))
      (node (ref "R42") (pin "2") (pinfunction "2_2") (pintype "passive"))
    )
    (net (code "72") (name "Net-(LED4B-B-)") (class "Default")
      (node (ref "LED4") (pin "5") (pinfunction "B-_5") (pintype "passive"))
      (node (ref "Q42") (pin "3") (pinfunction "C_3") (pintype "passive"))
    )
    (net (code "73") (name "Net-(LED4C-B+)") (class "Default")
      (node (ref "LED4") (pin "3") (pinfunction "B+_3") (pintype "passive"))
      (node (ref "R43") (pin "2") (pinfunction "2_2") (pintype "passive"))
    )
    (net (code "74") (name "Net-(LED4C-B-)") (class "Default")
      (node (ref "LED4") (pin "4") (pinfunction "B-_4") (pintype "passive"))
      (node (ref "Q43") (pin "3") (pinfunction "C_3") (pintype "passive"))
    )
    (net (code "75") (name "Net-(LED5A-B+)") (class "Default")
      (node (ref "LED5") (pin "1") (pinfunction "B+_1") (pintype "passive"))
      (node (ref "R51") (pin "2") (pinfunction "2_2") (pintype "passive"))
    )
    (net (code "76") (name "Net-(LED5A-B-)") (class "Default")
      (node (ref "LED5") (pin "6") (pinfunction "B-_6") (pintype "passive"))
      (node (ref "Q51") (pin "3") (pinfunction "C_3") (pintype "passive"))
    )
    (net (code "77") (name "Net-(LED5B-B+)") (class "Default")
      (node (ref "LED5") (pin "2") (pinfunction "B+_2") (pintype "passive"))
      (node (ref "R52") (pin "2") (pinfunction "2_2") (pintype "passive"))
    )
    (net (code "78") (name "Net-(LED5B-B-)") (class "Default")
      (node (ref "LED5") (pin "5") (pinfunction "B-_5") (pintype "passive"))
      (node (ref "Q52") (pin "3") (pinfunction "C_3") (pintype "passive"))
    )
    (net (code "79") (name "Net-(LED5C-B+)") (class "Default")
      (node (ref "LED5") (pin "3") (pinfunction "B+_3") (pintype "passive"))
      (node (ref "R53") (pin "2") (pinfunction "2_2") (pintype "passive"))
    )
    (net (code "80") (name "Net-(LED5C-B-)") (class "Default")
      (node (ref "LED5") (pin "4") (pinfunction "B-_4") (pintype "passive"))
      (node (ref "Q53") (pin "3") (pinfunction "C_3") (pintype "passive"))
    )
    (net (code "81") (name "Net-(Q1-In)") (class "Default")
      (node (ref "CI") (pin "1") (pinfunction "1_1") (pintype "passive"))
      (node (ref "POW") (pin "1") (pinfunction "1_1") (pintype "passive"))
      (node (ref "Q1") (pin "1") (pinfunction "In_1") (pintype "passive"))
    )
    (net (code "82") (name "Net-(Q11-B)") (class "Default")
      (node (ref "Q11") (pin "2") (pinfunction "B_2") (pintype "passive"))
      (node (ref "Rb11") (pin "2") (pinfunction "2_2") (pintype "passive"))
    )
    (net (code "83") (name "Net-(Q12-B)") (class "Default")
      (node (ref "Q12") (pin "2") (pinfunction "B_2") (pintype "passive"))
      (node (ref "Rb12") (pin "2") (pinfunction "2_2") (pintype "passive"))
    )
    (net (code "84") (name "Net-(Q13-B)") (class "Default")
      (node (ref "Q13") (pin "2") (pinfunction "B_2") (pintype "passive"))
      (node (ref "Rb13") (pin "2") (pinfunction "2_2") (pintype "passive"))
    )
    (net (code "85") (name "Net-(Q14-B)") (class "Default")
      (node (ref "Q14") (pin "2") (pinfunction "B_2") (pintype "passive"))
      (node (ref "Rb14") (pin "2") (pinfunction "2_2") (pintype "passive"))
    )
    (net (code "86") (name "Net-(Q21-B)") (class "Default")
      (node (ref "Q21") (pin "2") (pinfunction "B_2") (pintype "passive"))
      (node (ref "Rb21") (pin "2") (pinfunction "2_2") (pintype "passive"))
    )
    (net (code "87") (name "Net-(Q22-B)") (class "Default")
      (node (ref "Q22") (pin "2") (pinfunction "B_2") (pintype "passive"))
      (node (ref "Rb22") (pin "2") (pinfunction "2_2") (pintype "passive"))
    )
    (net (code "88") (name "Net-(Q23-B)") (class "Default")
      (node (ref "Q23") (pin "2") (pinfunction "B_2") (pintype "passive"))
      (node (ref "Rb23") (pin "2") (pinfunction "2_2") (pintype "passive"))
    )
    (net (code "89") (name "Net-(Q24-B)") (class "Default")
      (node (ref "Q24") (pin "2") (pinfunction "B_2") (pintype "passive"))
      (node (ref "Rb24") (pin "2") (pinfunction "2_2") (pintype "passive"))
    )
    (net (code "90") (name "Net-(Q31-B)") (class "Default")
      (node (ref "Q31") (pin "2") (pinfunction "B_2") (pintype "passive"))
      (node (ref "Rb31") (pin "2") (pinfunction "2_2") (pintype "passive"))
    )
    (net (code "91") (name "Net-(Q32-B)") (class "Default")
      (node (ref "Q32") (pin "2") (pinfunction "B_2") (pintype "passive"))
      (node (ref "Rb32") (pin "2") (pinfunction "2_2") (pintype "passive"))
    )
    (net (code "92") (name "Net-(Q33-B)") (class "Default")
      (node (ref "Q33") (pin "2") (pinfunction "B_2") (pintype "passive"))
      (node (ref "Rb33") (pin "2") (pinfunction "2_2") (pintype "passive"))
    )
    (net (code "93") (name "Net-(Q34-B)") (class "Default")
      (node (ref "Q34") (pin "2") (pinfunction "B_2") (pintype "passive"))
      (node (ref "Rb34") (pin "2") (pinfunction "2_2") (pintype "passive"))
    )
    (net (code "94") (name "Net-(Q41-B)") (class "Default")
      (node (ref "Q41") (pin "2") (pinfunction "B_2") (pintype "passive"))
      (node (ref "Rb41") (pin "2") (pinfunction "2_2") (pintype "passive"))
    )
    (net (code "95") (name "Net-(Q42-B)") (class "Default")
      (node (ref "Q42") (pin "2") (pinfunction "B_2") (pintype "passive"))
      (node (ref "Rb42") (pin "2") (pinfunction "2_2") (pintype "passive"))
    )
    (net (code "96") (name "Net-(Q43-B)") (class "Default")
      (node (ref "Q43") (pin "2") (pinfunction "B_2") (pintype "passive"))
      (node (ref "Rb43") (pin "2") (pinfunction "2_2") (pintype "passive"))
    )
    (net (code "97") (name "Net-(Q44-B)") (class "Default")
      (node (ref "Q44") (pin "2") (pinfunction "B_2") (pintype "passive"))
      (node (ref "Rb44") (pin "2") (pinfunction "2_2") (pintype "passive"))
    )
    (net (code "98") (name "Net-(Q51-B)") (class "Default")
      (node (ref "Q51") (pin "2") (pinfunction "B_2") (pintype "passive"))
      (node (ref "Rb51") (pin "2") (pinfunction "2_2") (pintype "passive"))
    )
    (net (code "99") (name "Net-(Q52-B)") (class "Default")
      (node (ref "Q52") (pin "2") (pinfunction "B_2") (pintype "passive"))
      (node (ref "Rb52") (pin "2") (pinfunction "2_2") (pintype "passive"))
    )
    (net (code "100") (name "Net-(Q53-B)") (class "Default")
      (node (ref "Q53") (pin "2") (pinfunction "B_2") (pintype "passive"))
      (node (ref "Rb53") (pin "2") (pinfunction "2_2") (pintype "passive"))
    )
    (net (code "101") (name "Net-(Q54-B)") (class "Default")
      (node (ref "Q54") (pin "2") (pinfunction "B_2") (pintype "passive"))
      (node (ref "Rb54") (pin "2") (pinfunction "2_2") (pintype "passive"))
    )
    (net (code "102") (name "Net-(R2-Pad2)") (class "Default")
      (node (ref "R2") (pin "2") (pinfunction "2_2") (pintype "passive"))
      (node (ref "RST") (pin "1") (pinfunction "1_1") (pintype "passive"))
    )
    (net (code "103") (name "VCC") (class "Default")
      (node (ref "C1") (pin "1") (pinfunction "1_1") (pintype "passive"))
      (node (ref "C4") (pin "1") (pinfunction "1_1") (pintype "passive"))
      (node (ref "C5") (pin "1") (pinfunction "1_1") (pintype "passive"))
      (node (ref "PS1") (pin "1") (pinfunction "COMMON_1") (pintype "passive"))
      (node (ref "R11") (pin "1") (pinfunction "1_1") (pintype "passive"))
      (node (ref "R12") (pin "1") (pinfunction "1_1") (pintype "passive"))
      (node (ref "R13") (pin "1") (pinfunction "1_1") (pintype "passive"))
      (node (ref "R14") (pin "1") (pinfunction "1_1") (pintype "passive"))
      (node (ref "R21") (pin "1") (pinfunction "1_1") (pintype "passive"))
      (node (ref "R22") (pin "1") (pinfunction "1_1") (pintype "passive"))
      (node (ref "R23") (pin "1") (pinfunction "1_1") (pintype "passive"))
      (node (ref "R24") (pin "1") (pinfunction "1_1") (pintype "passive"))
      (node (ref "R31") (pin "1") (pinfunction "1_1") (pintype "passive"))
      (node (ref "R32") (pin "1") (pinfunction "1_1") (pintype "passive"))
      (node (ref "R33") (pin "1") (pinfunction "1_1") (pintype "passive"))
      (node (ref "R34") (pin "1") (pinfunction "1_1") (pintype "passive"))
      (node (ref "R41") (pin "1") (pinfunction "1_1") (pintype "passive"))
      (node (ref "R42") (pin "1") (pinfunction "1_1") (pintype "passive"))
      (node (ref "R43") (pin "1") (pinfunction "1_1") (pintype "passive"))
      (node (ref "R44") (pin "1") (pinfunction "1_1") (pintype "passive"))
      (node (ref "R45") (pin "1") (pinfunction "1_1") (pintype "passive"))
      (node (ref "R51") (pin "1") (pinfunction "1_1") (pintype "passive"))
      (node (ref "R52") (pin "1") (pinfunction "1_1") (pintype "passive"))
      (node (ref "R53") (pin "1") (pinfunction "1_1") (pintype "passive"))
      (node (ref "RP") (pin "1") (pinfunction "1_1") (pintype "passive"))
      (node (ref "RST") (pin "2") (pinfunction "2_2") (pintype "passive"))
      (node (ref "U1") (pin "38") (pinfunction "VCC_38") (pintype "passive"))
    )
    (net (code "104") (name "unconnected-(U1-ALE-Pad27)") (class "Default")
      (node (ref "U1") (pin "27") (pinfunction "ALE_27") (pintype "passive"))
    )
    (net (code "105") (name "unconnected-(U1-EA-Pad29)") (class "Default")
      (node (ref "U1") (pin "29") (pinfunction "EA_29") (pintype "passive"))
    )
    (net (code "106") (name "unconnected-(U1-P3.2-Pad8)") (class "Default")
      (node (ref "U1") (pin "8") (pinfunction "P3.2_8") (pintype "passive"))
    )
    (net (code "107") (name "unconnected-(U1-P3.3-Pad9)") (class "Default")
      (node (ref "U1") (pin "9") (pinfunction "P3.3_9") (pintype "passive"))
    )
    (net (code "108") (name "unconnected-(U1-P3.4-Pad10)") (class "Default")
      (node (ref "U1") (pin "10") (pinfunction "P3.4_10") (pintype "passive"))
    )
    (net (code "109") (name "unconnected-(U1-P3.5-Pad11)") (class "Default")
      (node (ref "U1") (pin "11") (pinfunction "P3.5_11") (pintype "passive"))
    )
    (net (code "110") (name "unconnected-(U1-P3.6-Pad12)") (class "Default")
      (node (ref "U1") (pin "12") (pinfunction "P3.6_12") (pintype "passive"))
    )
    (net (code "111") (name "unconnected-(U1-P3.7-Pad13)") (class "Default")
      (node (ref "U1") (pin "13") (pinfunction "P3.7_13") (pintype "passive"))
    )
    (net (code "112") (name "unconnected-(U1-P4.0-Pad17)") (class "Default")
      (node (ref "U1") (pin "17") (pinfunction "P4.0_17") (pintype "passive"))
    )
    (net (code "113") (name "unconnected-(U1-P4.1-Pad28)") (class "Default")
      (node (ref "U1") (pin "28") (pinfunction "P4.1_28") (pintype "passive"))
    )
    (net (code "114") (name "unconnected-(U1-P4.2-Pad39)") (class "Default")
      (node (ref "U1") (pin "39") (pinfunction "P4.2_39") (pintype "passive"))
    )
    (net (code "115") (name "unconnected-(U1-P4.3-Pad6)") (class "Default")
      (node (ref "U1") (pin "6") (pinfunction "P4.3_6") (pintype "passive"))
    )
    (net (code "116") (name "unconnected-(U1-PSEN-Pad26)") (class "Default")
      (node (ref "U1") (pin "26") (pinfunction "PSEN_26") (pintype "passive"))
    )
    (net (code "117") (name "unconnected-(U1-RST-Pad4)") (class "Default")
      (node (ref "U1") (pin "4") (pinfunction "RST_4") (pintype "passive"))
    )
    (net (code "118") (name "unconnected-(U1-XTAL1-Pad15)") (class "Default")
      (node (ref "U1") (pin "15") (pinfunction "XTAL1_15") (pintype "passive"))
    )
    (net (code "119") (name "unconnected-(U1-XTAL2-Pad14)") (class "Default")
      (node (ref "U1") (pin "14") (pinfunction "XTAL2_14") (pintype "passive"))
    )
    (net (code "120") (name "unconnected-(USB1-Pad2)") (class "Default")
      (node (ref "USB1") (pin "2") (pinfunction "2_2") (pintype "passive"))
    )
    (net (code "121") (name "unconnected-(USB1-Pad3)") (class "Default")
      (node (ref "USB1") (pin "3") (pinfunction "3_3") (pintype "passive"))
    )
    (net (code "122") (name "unconnected-(USB1-Pad4)") (class "Default")
      (node (ref "USB1") (pin "4") (pinfunction "4_4") (pintype "passive"))
    )
  )
)
